# STM32WB55_Main_MCU.net
KiCad netlist of a schematic drawn in Altium Designer
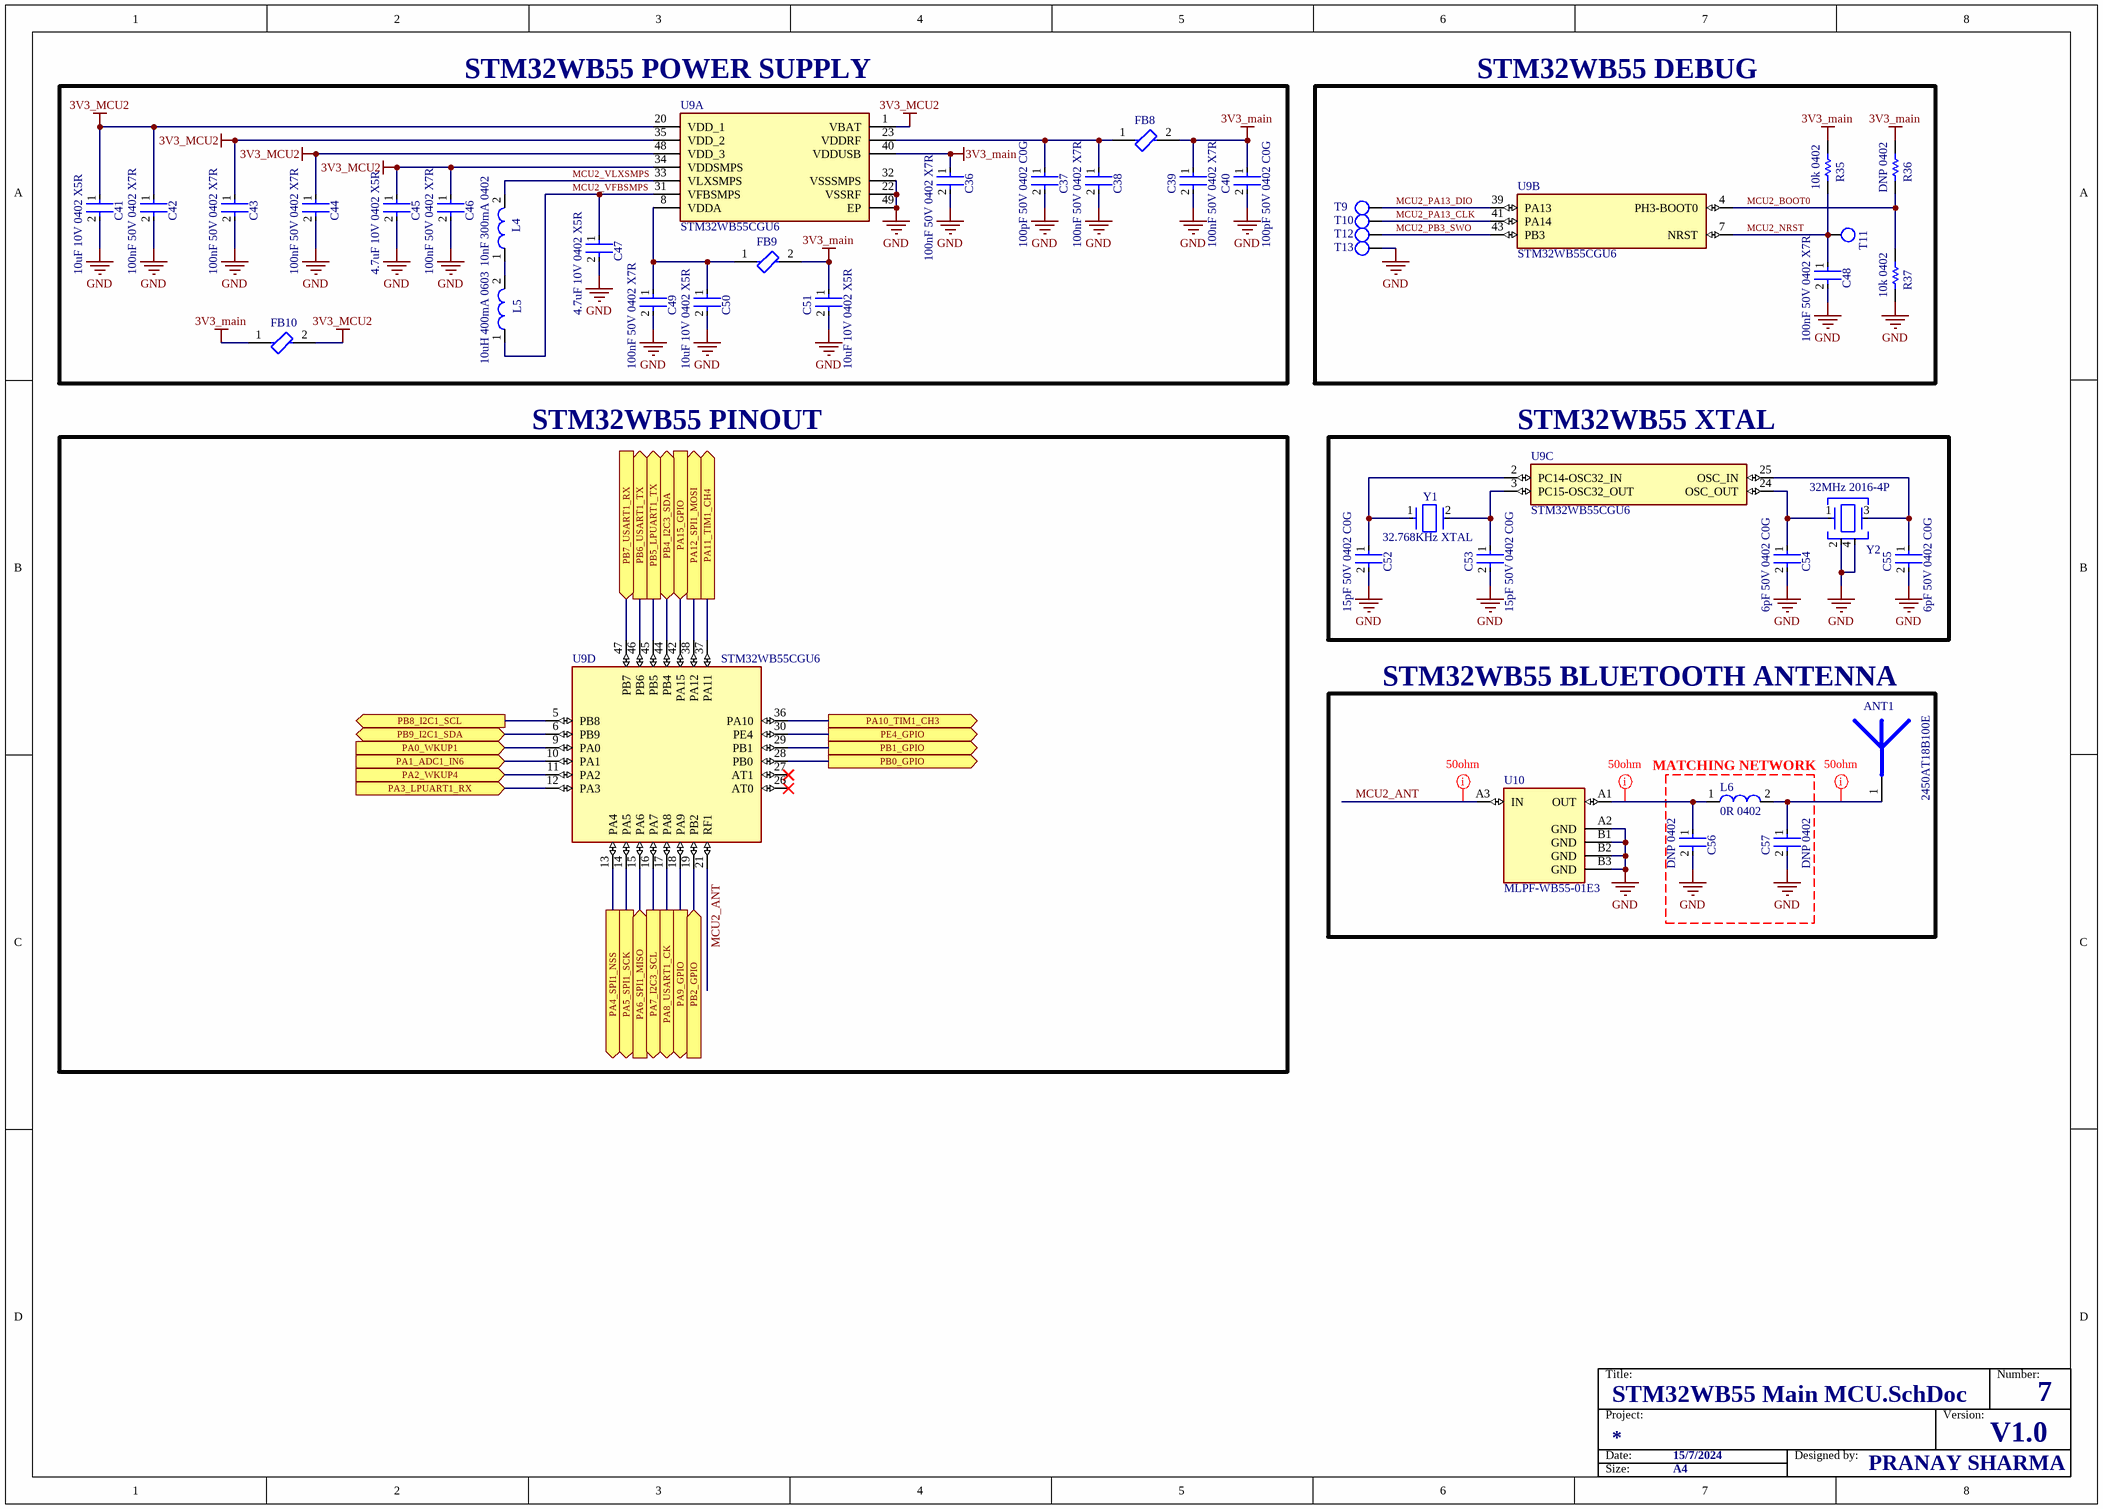
[diagram p0: STM32WB55 Main MCU.SchDoc]

(export (version "E")
  (design (tool "Eeschema 10.0.6"))
  (components
    (comp (ref "ANT1")
      (value "2450AT18B100E")
      (footprint "Miscellaneous_Lib:2450AT18B100E IPC-C")
      (libsource (lib "Miscellaneous_Lib") (part "2450AT18B100E"))
    )
    (comp (ref "C36")
      (value "100nF 50V 0402 X7R")
      (footprint "Res, Cap, Ind, LED, FB_Lib:0402 IPC CLASS C CAPACITOR")
      (libsource (lib "Capacitor_Lib") (part "100nF 50V 0402 X7R"))
    )
    (comp (ref "C37")
      (value "100pF 50V 0402 C0G")
      (footprint "Res, Cap, Ind, LED, FB_Lib:0402 IPC CLASS C CAPACITOR")
      (libsource (lib "Capacitor_Lib") (part "100pF 50V 0402 C0G"))
    )
    (comp (ref "C38")
      (value "100nF 50V 0402 X7R")
      (footprint "Res, Cap, Ind, LED, FB_Lib:0402 IPC CLASS C CAPACITOR")
      (libsource (lib "Capacitor_Lib") (part "100nF 50V 0402 X7R"))
    )
    (comp (ref "C39")
      (value "100nF 50V 0402 X7R")
      (footprint "Res, Cap, Ind, LED, FB_Lib:0402 IPC CLASS C CAPACITOR")
      (libsource (lib "Capacitor_Lib") (part "100nF 50V 0402 X7R"))
    )
    (comp (ref "C40")
      (value "100pF 50V 0402 C0G")
      (footprint "Res, Cap, Ind, LED, FB_Lib:0402 IPC CLASS C CAPACITOR")
      (libsource (lib "Capacitor_Lib") (part "100pF 50V 0402 C0G"))
    )
    (comp (ref "C41")
      (value "10uF 10V 0402 X5R")
      (footprint "Res, Cap, Ind, LED, FB_Lib:0402 IPC CLASS C CAPACITOR")
      (libsource (lib "Capacitor_Lib") (part "10uF 10V 0402 X5R"))
    )
    (comp (ref "C42")
      (value "100nF 50V 0402 X7R")
      (footprint "Res, Cap, Ind, LED, FB_Lib:0402 IPC CLASS C CAPACITOR")
      (libsource (lib "Capacitor_Lib") (part "100nF 50V 0402 X7R"))
    )
    (comp (ref "C43")
      (value "100nF 50V 0402 X7R")
      (footprint "Res, Cap, Ind, LED, FB_Lib:0402 IPC CLASS C CAPACITOR")
      (libsource (lib "Capacitor_Lib") (part "100nF 50V 0402 X7R"))
    )
    (comp (ref "C44")
      (value "100nF 50V 0402 X7R")
      (footprint "Res, Cap, Ind, LED, FB_Lib:0402 IPC CLASS C CAPACITOR")
      (libsource (lib "Capacitor_Lib") (part "100nF 50V 0402 X7R"))
    )
    (comp (ref "C45")
      (value "4.7uF 10V 0402 X5R")
      (footprint "Res, Cap, Ind, LED, FB_Lib:0402 IPC CLASS C CAPACITOR")
      (libsource (lib "Capacitor_Lib") (part "4.7uF 10V 0402 X5R"))
    )
    (comp (ref "C46")
      (value "100nF 50V 0402 X7R")
      (footprint "Res, Cap, Ind, LED, FB_Lib:0402 IPC CLASS C CAPACITOR")
      (libsource (lib "Capacitor_Lib") (part "100nF 50V 0402 X7R"))
    )
    (comp (ref "C47")
      (value "4.7uF 10V 0402 X5R")
      (footprint "Res, Cap, Ind, LED, FB_Lib:0402 IPC CLASS C CAPACITOR")
      (libsource (lib "Capacitor_Lib") (part "4.7uF 10V 0402 X5R"))
    )
    (comp (ref "C48")
      (value "100nF 50V 0402 X7R")
      (footprint "Res, Cap, Ind, LED, FB_Lib:0402 IPC CLASS C CAPACITOR")
      (libsource (lib "Capacitor_Lib") (part "100nF 50V 0402 X7R"))
    )
    (comp (ref "C49")
      (value "100nF 50V 0402 X7R")
      (footprint "Res, Cap, Ind, LED, FB_Lib:0402 IPC CLASS C CAPACITOR")
      (libsource (lib "Capacitor_Lib") (part "100nF 50V 0402 X7R"))
    )
    (comp (ref "C50")
      (value "10uF 10V 0402 X5R")
      (footprint "Res, Cap, Ind, LED, FB_Lib:0402 IPC CLASS C CAPACITOR")
      (libsource (lib "Capacitor_Lib") (part "10uF 10V 0402 X5R"))
    )
    (comp (ref "C51")
      (value "10uF 10V 0402 X5R")
      (footprint "Res, Cap, Ind, LED, FB_Lib:0402 IPC CLASS C CAPACITOR")
      (libsource (lib "Capacitor_Lib") (part "10uF 10V 0402 X5R"))
    )
    (comp (ref "C52")
      (value "15pF 50V 0402 C0G")
      (footprint "Res, Cap, Ind, LED, FB_Lib:0402 IPC CLASS C CAPACITOR")
      (libsource (lib "Capacitor_Lib") (part "15pF 50V 0402 C0G"))
    )
    (comp (ref "C53")
      (value "15pF 50V 0402 C0G")
      (footprint "Res, Cap, Ind, LED, FB_Lib:0402 IPC CLASS C CAPACITOR")
      (libsource (lib "Capacitor_Lib") (part "15pF 50V 0402 C0G"))
    )
    (comp (ref "C54")
      (value "6pF 50V 0402 C0G")
      (footprint "Res, Cap, Ind, LED, FB_Lib:0402 IPC CLASS C CAPACITOR")
      (libsource (lib "Capacitor_Lib") (part "6pF 50V 0402 C0G"))
    )
    (comp (ref "C55")
      (value "6pF 50V 0402 C0G")
      (footprint "Res, Cap, Ind, LED, FB_Lib:0402 IPC CLASS C CAPACITOR")
      (libsource (lib "Capacitor_Lib") (part "6pF 50V 0402 C0G"))
    )
    (comp (ref "C56")
      (value "DNP 0402")
      (footprint "Res, Cap, Ind, LED, FB_Lib:0402 IPC CLASS C CAPACITOR")
      (libsource (lib "Capacitor_Lib") (part "100nF 50V 0402 X7R"))
    )
    (comp (ref "C57")
      (value "DNP 0402")
      (footprint "Res, Cap, Ind, LED, FB_Lib:0402 IPC CLASS C CAPACITOR")
      (libsource (lib "Capacitor_Lib") (part "100nF 50V 0402 X7R"))
    )
    (comp (ref "FB8")
      (value "BLM15AX102SN1D")
      (footprint "Res, Cap, Ind, LED, FB_Lib:0402 IPC CLASS C FERRITE BEAD")
      (libsource (lib "Ferrite_Bead_Lib") (part "BLM15AX102SN1D"))
    )
    (comp (ref "FB9")
      (value "BLM15AX102SN1D")
      (footprint "Res, Cap, Ind, LED, FB_Lib:0402 IPC CLASS C FERRITE BEAD")
      (libsource (lib "Ferrite_Bead_Lib") (part "BLM15AX102SN1D"))
    )
    (comp (ref "FB10")
      (value "BLM15AX102SN1D")
      (footprint "Res, Cap, Ind, LED, FB_Lib:0402 IPC CLASS C FERRITE BEAD")
      (libsource (lib "Ferrite_Bead_Lib") (part "BLM15AX102SN1D"))
    )
    (comp (ref "L4")
      (value "10nF 300mA 0402")
      (footprint "Res, Cap, Ind, LED, FB_Lib:0402 IPC CLASS C FERRITE BEAD")
      (libsource (lib "Inductor_Lib") (part "SDCL1005C10NJTDF"))
    )
    (comp (ref "L5")
      (value "10uH 400mA 0603")
      (footprint "Res, Cap, Ind, LED, FB_Lib:0603 IPC CLASS C INDUCTOR")
      (libsource (lib "Inductor_Lib") (part "MGFL1608F100MT-LF"))
    )
    (comp (ref "L6")
      (value "0R 0402")
      (footprint "Res, Cap, Ind, LED, FB_Lib:0402 IPC CLASS C FERRITE BEAD")
      (libsource (lib "Inductor_Lib") (part "SDCL1005C10NJTDF"))
    )
    (comp (ref "R35")
      (value "10k 0402")
      (footprint "Res, Cap, Ind, LED, FB_Lib:0402 IPC CLASS C RESISTOR")
      (libsource (lib "Resistor_Lib") (part "10k 1% 0402"))
    )
    (comp (ref "R36")
      (value "DNP 0402")
      (footprint "Res, Cap, Ind, LED, FB_Lib:0402 IPC CLASS C RESISTOR")
      (libsource (lib "Resistor_Lib") (part "0R 1% 0402"))
    )
    (comp (ref "R37")
      (value "10k 0402")
      (footprint "Res, Cap, Ind, LED, FB_Lib:0402 IPC CLASS C RESISTOR")
      (libsource (lib "Resistor_Lib") (part "10k 1% 0402"))
    )
    (comp (ref "T9")
      (value "Test Point TH")
      (footprint "Miscellaneous_Lib:Test Point TH")
      (libsource (lib "Miscellaneous_Lib") (part "Test Point TH"))
    )
    (comp (ref "T10")
      (value "Test Point TH")
      (footprint "Miscellaneous_Lib:Test Point TH")
      (libsource (lib "Miscellaneous_Lib") (part "Test Point TH"))
    )
    (comp (ref "T11")
      (value "Test Point TH")
      (footprint "Miscellaneous_Lib:Test Point TH")
      (libsource (lib "Miscellaneous_Lib") (part "Test Point TH"))
    )
    (comp (ref "T12")
      (value "Test Point TH")
      (footprint "Miscellaneous_Lib:Test Point TH")
      (libsource (lib "Miscellaneous_Lib") (part "Test Point TH"))
    )
    (comp (ref "T13")
      (value "Test Point TH")
      (footprint "Miscellaneous_Lib:Test Point TH")
      (libsource (lib "Miscellaneous_Lib") (part "Test Point TH"))
    )
    (comp (ref "U9")
      (value "STM32WB55CGU6")
      (footprint "MCU_MPU_Lib:UFQFPN48 IPC-C")
      (libsource (lib "MCU_MPU_Lib") (part "STM32WB55CGU6"))
    )
    (comp (ref "U10")
      (value "MLPF-WB55-01E3")
      (footprint "Miscellaneous_Lib:MLPF-WB55-01E3")
      (libsource (lib "Miscellaneous_Lib") (part "MLPF-WB55-01E3"))
    )
    (comp (ref "Y1")
      (value "32.768KHz XTAL")
      (footprint "Crystals_and_Oscillators_Lib:SMD3215-2P IPC-C")
      (libsource (lib "Crystals_and_Oscillators_Lib") (part "H31003271C2070CY"))
    )
    (comp (ref "Y2")
      (value "32MHz 2016-4P")
      (footprint "Crystals_and_Oscillators_Lib:SMD2016-4P IPC-C")
      (libsource (lib "Crystals_and_Oscillators_Lib") (part "32MHz 2016-4P"))
    )
  )
  (nets
    (net (code "1") (name "/MCU2_ANT") (class "Default")
      (node (ref "U10") (pin "A3") (pinfunction "IN_A3") (pintype "bidirectional"))
      (node (ref "U9") (pin "21") (pinfunction "RF1_21") (pintype "bidirectional"))
    )
    (net (code "2") (name "/MCU2_BOOT0") (class "Default")
      (node (ref "R36") (pin "1") (pinfunction "1_1") (pintype "passive"))
      (node (ref "R37") (pin "2") (pinfunction "2_2") (pintype "passive"))
      (node (ref "U9") (pin "4") (pinfunction "PH3-BOOT0_4") (pintype "bidirectional"))
    )
    (net (code "3") (name "/MCU2_NRST") (class "Default")
      (node (ref "C48") (pin "1") (pinfunction "1_1") (pintype "passive"))
      (node (ref "R35") (pin "1") (pinfunction "1_1") (pintype "passive"))
      (node (ref "T11") (pin "0") (pinfunction "0_0") (pintype "passive"))
      (node (ref "U9") (pin "7") (pinfunction "NRST_7") (pintype "bidirectional"))
    )
    (net (code "4") (name "/MCU2_PA13_CLK") (class "Default")
      (node (ref "T10") (pin "0") (pinfunction "0_0") (pintype "passive"))
      (node (ref "U9") (pin "41") (pinfunction "PA14_41") (pintype "bidirectional"))
    )
    (net (code "5") (name "/MCU2_PA13_DIO") (class "Default")
      (node (ref "T9") (pin "0") (pinfunction "0_0") (pintype "passive"))
      (node (ref "U9") (pin "39") (pinfunction "PA13_39") (pintype "bidirectional"))
    )
    (net (code "6") (name "/MCU2_PB3_SWO") (class "Default")
      (node (ref "T12") (pin "0") (pinfunction "0_0") (pintype "passive"))
      (node (ref "U9") (pin "43") (pinfunction "PB3_43") (pintype "bidirectional"))
    )
    (net (code "7") (name "/MCU2_VFBSMPS") (class "Default")
      (node (ref "C47") (pin "1") (pinfunction "1_1") (pintype "passive"))
      (node (ref "L5") (pin "1") (pinfunction "1_1") (pintype "passive"))
      (node (ref "U9") (pin "31") (pinfunction "VFBSMPS_31") (pintype "power_in"))
    )
    (net (code "8") (name "/MCU2_VLXSMPS") (class "Default")
      (node (ref "L4") (pin "2") (pinfunction "2_2") (pintype "passive"))
      (node (ref "U9") (pin "33") (pinfunction "VLXSMPS_33") (pintype "power_in"))
    )
    (net (code "9") (name "/PA0_WKUP1") (class "Default")
      (node (ref "U9") (pin "9") (pinfunction "PA0_9") (pintype "bidirectional"))
    )
    (net (code "10") (name "/PA1_ADC1_IN6") (class "Default")
      (node (ref "U9") (pin "10") (pinfunction "PA1_10") (pintype "bidirectional"))
    )
    (net (code "11") (name "/PA2_WKUP4") (class "Default")
      (node (ref "U9") (pin "11") (pinfunction "PA2_11") (pintype "bidirectional"))
    )
    (net (code "12") (name "/PA3_LPUART1_RX") (class "Default")
      (node (ref "U9") (pin "12") (pinfunction "PA3_12") (pintype "bidirectional"))
    )
    (net (code "13") (name "/PA4_SPI1_NSS") (class "Default")
      (node (ref "U9") (pin "13") (pinfunction "PA4_13") (pintype "bidirectional"))
    )
    (net (code "14") (name "/PA5_SPI1_SCK") (class "Default")
      (node (ref "U9") (pin "14") (pinfunction "PA5_14") (pintype "bidirectional"))
    )
    (net (code "15") (name "/PA6_SPI1_MISO") (class "Default")
      (node (ref "U9") (pin "15") (pinfunction "PA6_15") (pintype "bidirectional"))
    )
    (net (code "16") (name "/PA7_I2C3_SCL") (class "Default")
      (node (ref "U9") (pin "16") (pinfunction "PA7_16") (pintype "bidirectional"))
    )
    (net (code "17") (name "/PA8_USART1_CK") (class "Default")
      (node (ref "U9") (pin "17") (pinfunction "PA8_17") (pintype "bidirectional"))
    )
    (net (code "18") (name "/PA9_GPIO") (class "Default")
      (node (ref "U9") (pin "18") (pinfunction "PA9_18") (pintype "bidirectional"))
    )
    (net (code "19") (name "/PA10_TIM1_CH3") (class "Default")
      (node (ref "U9") (pin "36") (pinfunction "PA10_36") (pintype "bidirectional"))
    )
    (net (code "20") (name "/PA11_TIM1_CH4") (class "Default")
      (node (ref "U9") (pin "37") (pinfunction "PA11_37") (pintype "bidirectional"))
    )
    (net (code "21") (name "/PA12_SPI1_MOSI") (class "Default")
      (node (ref "U9") (pin "38") (pinfunction "PA12_38") (pintype "bidirectional"))
    )
    (net (code "22") (name "/PA15_GPIO") (class "Default")
      (node (ref "U9") (pin "42") (pinfunction "PA15_42") (pintype "bidirectional"))
    )
    (net (code "23") (name "/PB0_GPIO") (class "Default")
      (node (ref "U9") (pin "28") (pinfunction "PB0_28") (pintype "bidirectional"))
    )
    (net (code "24") (name "/PB1_GPIO") (class "Default")
      (node (ref "U9") (pin "29") (pinfunction "PB1_29") (pintype "bidirectional"))
    )
    (net (code "25") (name "/PB2_GPIO") (class "Default")
      (node (ref "U9") (pin "19") (pinfunction "PB2_19") (pintype "bidirectional"))
    )
    (net (code "26") (name "/PB4_I2C3_SDA") (class "Default")
      (node (ref "U9") (pin "44") (pinfunction "PB4_44") (pintype "bidirectional"))
    )
    (net (code "27") (name "/PB5_LPUART1_TX") (class "Default")
      (node (ref "U9") (pin "45") (pinfunction "PB5_45") (pintype "bidirectional"))
    )
    (net (code "28") (name "/PB6_USART1_TX") (class "Default")
      (node (ref "U9") (pin "46") (pinfunction "PB6_46") (pintype "bidirectional"))
    )
    (net (code "29") (name "/PB7_USART1_RX") (class "Default")
      (node (ref "U9") (pin "47") (pinfunction "PB7_47") (pintype "bidirectional"))
    )
    (net (code "30") (name "/PB8_I2C1_SCL") (class "Default")
      (node (ref "U9") (pin "5") (pinfunction "PB8_5") (pintype "bidirectional"))
    )
    (net (code "31") (name "/PB9_I2C1_SDA") (class "Default")
      (node (ref "U9") (pin "6") (pinfunction "PB9_6") (pintype "bidirectional"))
    )
    (net (code "32") (name "/PE4_GPIO") (class "Default")
      (node (ref "U9") (pin "30") (pinfunction "PE4_30") (pintype "bidirectional"))
    )
    (net (code "33") (name "3V3_MCU2") (class "Default")
      (node (ref "C41") (pin "1") (pinfunction "1_1") (pintype "passive"))
      (node (ref "C42") (pin "1") (pinfunction "1_1") (pintype "passive"))
      (node (ref "C43") (pin "1") (pinfunction "1_1") (pintype "passive"))
      (node (ref "C44") (pin "1") (pinfunction "1_1") (pintype "passive"))
      (node (ref "C45") (pin "1") (pinfunction "1_1") (pintype "passive"))
      (node (ref "C46") (pin "1") (pinfunction "1_1") (pintype "passive"))
      (node (ref "FB10") (pin "2") (pinfunction "2_2") (pintype "passive"))
      (node (ref "U9") (pin "1") (pinfunction "VBAT_1") (pintype "power_in"))
      (node (ref "U9") (pin "20") (pinfunction "VDD_1_20") (pintype "power_in"))
      (node (ref "U9") (pin "34") (pinfunction "VDDSMPS_34") (pintype "power_in"))
      (node (ref "U9") (pin "35") (pinfunction "VDD_2_35") (pintype "power_in"))
      (node (ref "U9") (pin "48") (pinfunction "VDD_3_48") (pintype "power_in"))
    )
    (net (code "34") (name "3V3_main") (class "Default")
      (node (ref "C36") (pin "1") (pinfunction "1_1") (pintype "passive"))
      (node (ref "C39") (pin "1") (pinfunction "1_1") (pintype "passive"))
      (node (ref "C40") (pin "1") (pinfunction "1_1") (pintype "passive"))
      (node (ref "C51") (pin "1") (pinfunction "1_1") (pintype "passive"))
      (node (ref "FB10") (pin "1") (pinfunction "1_1") (pintype "passive"))
      (node (ref "FB8") (pin "2") (pinfunction "2_2") (pintype "passive"))
      (node (ref "FB9") (pin "2") (pinfunction "2_2") (pintype "passive"))
      (node (ref "R35") (pin "2") (pinfunction "2_2") (pintype "passive"))
      (node (ref "R36") (pin "2") (pinfunction "2_2") (pintype "passive"))
      (node (ref "U9") (pin "40") (pinfunction "VDDUSB_40") (pintype "power_in"))
    )
    (net (code "35") (name "GND") (class "Default")
      (node (ref "C36") (pin "2") (pinfunction "2_2") (pintype "passive"))
      (node (ref "C37") (pin "2") (pinfunction "2_2") (pintype "passive"))
      (node (ref "C38") (pin "2") (pinfunction "2_2") (pintype "passive"))
      (node (ref "C39") (pin "2") (pinfunction "2_2") (pintype "passive"))
      (node (ref "C40") (pin "2") (pinfunction "2_2") (pintype "passive"))
      (node (ref "C41") (pin "2") (pinfunction "2_2") (pintype "passive"))
      (node (ref "C42") (pin "2") (pinfunction "2_2") (pintype "passive"))
      (node (ref "C43") (pin "2") (pinfunction "2_2") (pintype "passive"))
      (node (ref "C44") (pin "2") (pinfunction "2_2") (pintype "passive"))
      (node (ref "C45") (pin "2") (pinfunction "2_2") (pintype "passive"))
      (node (ref "C46") (pin "2") (pinfunction "2_2") (pintype "passive"))
      (node (ref "C47") (pin "2") (pinfunction "2_2") (pintype "passive"))
      (node (ref "C48") (pin "2") (pinfunction "2_2") (pintype "passive"))
      (node (ref "C49") (pin "2") (pinfunction "2_2") (pintype "passive"))
      (node (ref "C50") (pin "2") (pinfunction "2_2") (pintype "passive"))
      (node (ref "C51") (pin "2") (pinfunction "2_2") (pintype "passive"))
      (node (ref "C52") (pin "2") (pinfunction "2_2") (pintype "passive"))
      (node (ref "C53") (pin "2") (pinfunction "2_2") (pintype "passive"))
      (node (ref "C54") (pin "2") (pinfunction "2_2") (pintype "passive"))
      (node (ref "C55") (pin "2") (pinfunction "2_2") (pintype "passive"))
      (node (ref "C56") (pin "2") (pinfunction "2_2") (pintype "passive"))
      (node (ref "C57") (pin "2") (pinfunction "2_2") (pintype "passive"))
      (node (ref "R37") (pin "1") (pinfunction "1_1") (pintype "passive"))
      (node (ref "T13") (pin "0") (pinfunction "0_0") (pintype "passive"))
      (node (ref "U10") (pin "A2") (pinfunction "GND_A2") (pintype "power_in"))
      (node (ref "U10") (pin "B1") (pinfunction "GND_B1") (pintype "power_in"))
      (node (ref "U10") (pin "B2") (pinfunction "GND_B2") (pintype "power_in"))
      (node (ref "U10") (pin "B3") (pinfunction "GND_B3") (pintype "power_in"))
      (node (ref "U9") (pin "22") (pinfunction "VSSRF_22") (pintype "power_in"))
      (node (ref "U9") (pin "32") (pinfunction "VSSSMPS_32") (pintype "power_in"))
      (node (ref "U9") (pin "49") (pinfunction "EP_49") (pintype "power_in"))
      (node (ref "Y2") (pin "2") (pinfunction "2_2") (pintype "passive"))
      (node (ref "Y2") (pin "4") (pinfunction "4_4") (pintype "passive"))
    )
    (net (code "36") (name "Net-(ANT1-Pad1)") (class "Default")
      (node (ref "ANT1") (pin "1") (pinfunction "1_1") (pintype "passive"))
      (node (ref "C57") (pin "1") (pinfunction "1_1") (pintype "passive"))
      (node (ref "L6") (pin "2") (pinfunction "2_2") (pintype "passive"))
    )
    (net (code "37") (name "Net-(L4-Pad1)") (class "Default")
      (node (ref "L4") (pin "1") (pinfunction "1_1") (pintype "passive"))
      (node (ref "L5") (pin "2") (pinfunction "2_2") (pintype "passive"))
    )
    (net (code "38") (name "Net-(U9A-VDDA)") (class "Default")
      (node (ref "C49") (pin "1") (pinfunction "1_1") (pintype "passive"))
      (node (ref "C50") (pin "1") (pinfunction "1_1") (pintype "passive"))
      (node (ref "FB9") (pin "1") (pinfunction "1_1") (pintype "passive"))
      (node (ref "U9") (pin "8") (pinfunction "VDDA_8") (pintype "power_in"))
    )
    (net (code "39") (name "Net-(U9A-VDDRF)") (class "Default")
      (node (ref "C37") (pin "1") (pinfunction "1_1") (pintype "passive"))
      (node (ref "C38") (pin "1") (pinfunction "1_1") (pintype "passive"))
      (node (ref "FB8") (pin "1") (pinfunction "1_1") (pintype "passive"))
      (node (ref "U9") (pin "23") (pinfunction "VDDRF_23") (pintype "power_in"))
    )
    (net (code "40") (name "Net-(U9C-OSC_IN)") (class "Default")
      (node (ref "C55") (pin "1") (pinfunction "1_1") (pintype "passive"))
      (node (ref "U9") (pin "25") (pinfunction "OSC_IN_25") (pintype "bidirectional"))
      (node (ref "Y2") (pin "3") (pinfunction "2_3") (pintype "passive"))
    )
    (net (code "41") (name "Net-(U9C-OSC_OUT)") (class "Default")
      (node (ref "C54") (pin "1") (pinfunction "1_1") (pintype "passive"))
      (node (ref "U9") (pin "24") (pinfunction "OSC_OUT_24") (pintype "bidirectional"))
      (node (ref "Y2") (pin "1") (pinfunction "1_1") (pintype "passive"))
    )
    (net (code "42") (name "Net-(U9C-PC14-OSC32_IN)") (class "Default")
      (node (ref "C52") (pin "1") (pinfunction "1_1") (pintype "passive"))
      (node (ref "U9") (pin "2") (pinfunction "PC14-OSC32_IN_2") (pintype "bidirectional"))
      (node (ref "Y1") (pin "1") (pinfunction "1_1") (pintype "passive"))
    )
    (net (code "43") (name "Net-(U9C-PC15-OSC32_OUT)") (class "Default")
      (node (ref "C53") (pin "1") (pinfunction "1_1") (pintype "passive"))
      (node (ref "U9") (pin "3") (pinfunction "PC15-OSC32_OUT_3") (pintype "bidirectional"))
      (node (ref "Y1") (pin "2") (pinfunction "2_2") (pintype "passive"))
    )
    (net (code "44") (name "Net-(U10-OUT)") (class "Default")
      (node (ref "C56") (pin "1") (pinfunction "1_1") (pintype "passive"))
      (node (ref "L6") (pin "1") (pinfunction "1_1") (pintype "passive"))
      (node (ref "U10") (pin "A1") (pinfunction "OUT_A1") (pintype "bidirectional"))
    )
    (net (code "45") (name "unconnected-(U9D-AT0-Pad26)") (class "Default")
      (node (ref "U9") (pin "26") (pinfunction "AT0_26") (pintype "bidirectional+no_connect"))
    )
    (net (code "46") (name "unconnected-(U9D-AT1-Pad27)") (class "Default")
      (node (ref "U9") (pin "27") (pinfunction "AT1_27") (pintype "bidirectional+no_connect"))
    )
  )
)
